# MAG3110.net
KiCad netlist of a schematic drawn in EAGLE
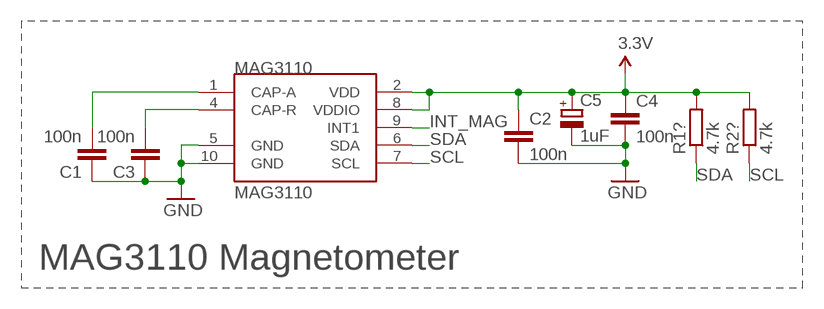
[diagram p0: schematic, sheet 1]

(export (version "E")
  (design (tool "Eeschema 10.0.6"))
  (components
    (comp (ref "C1")
      (value "100n")
      (footprint "eagle-import:C0805")
      (libsource (lib "eagle-import") (part "C-EUC0805"))
    )
    (comp (ref "C2")
      (value "100n")
      (footprint "eagle-import:C0805")
      (libsource (lib "eagle-import") (part "C-EUC0805"))
    )
    (comp (ref "C3")
      (value "100n")
      (footprint "eagle-import:C0805")
      (libsource (lib "eagle-import") (part "C-EUC0805"))
    )
    (comp (ref "C4")
      (value "100n")
      (footprint "eagle-import:C0805")
      (libsource (lib "eagle-import") (part "C-EUC0805"))
    )
    (comp (ref "C5")
      (value "1uF")
      (footprint "eagle-import:SMC_A")
      (libsource (lib "eagle-import") (part "CPOL-EUSMCA"))
    )
    (comp (ref "MAG3110")
      (value "MAG3110")
      (footprint "eagle-import:DFN-10")
      (libsource (lib "eagle-import") (part "MAG3110"))
    )
    (comp (ref "R1?")
      (value "4.7k")
      (footprint "eagle-import:R0805")
      (libsource (lib "eagle-import") (part "R-EU_R0805"))
    )
    (comp (ref "R2?")
      (value "4.7k")
      (footprint "eagle-import:R0805")
      (libsource (lib "eagle-import") (part "R-EU_R0805"))
    )
  )
  (nets
    (net (code "1") (name "/INT_MAG") (class "Default")
      (node (ref "MAG3110") (pin "9") (pinfunction "INT1_9") (pintype "bidirectional"))
    )
    (net (code "2") (name "/SCL") (class "Default")
      (node (ref "MAG3110") (pin "7") (pinfunction "SCL_7") (pintype "bidirectional"))
      (node (ref "R2?") (pin "1") (pinfunction "1_1") (pintype "passive"))
    )
    (net (code "3") (name "/SDA") (class "Default")
      (node (ref "MAG3110") (pin "6") (pinfunction "SDA_6") (pintype "bidirectional"))
      (node (ref "R1?") (pin "1") (pinfunction "1_1") (pintype "passive"))
    )
    (net (code "4") (name "3.3V") (class "Default")
      (node (ref "C2") (pin "1") (pinfunction "1_1") (pintype "passive"))
      (node (ref "C4") (pin "1") (pinfunction "1_1") (pintype "passive"))
      (node (ref "C5") (pin "+") (pinfunction "+_+") (pintype "passive"))
      (node (ref "MAG3110") (pin "2") (pinfunction "VDD_2") (pintype "bidirectional"))
      (node (ref "MAG3110") (pin "8") (pinfunction "VDDIO_8") (pintype "bidirectional"))
      (node (ref "R1?") (pin "2") (pinfunction "2_2") (pintype "passive"))
      (node (ref "R2?") (pin "2") (pinfunction "2_2") (pintype "passive"))
    )
    (net (code "5") (name "GND") (class "Default")
      (node (ref "C1") (pin "1") (pinfunction "1_1") (pintype "passive"))
      (node (ref "C2") (pin "2") (pinfunction "2_2") (pintype "passive"))
      (node (ref "C3") (pin "1") (pinfunction "1_1") (pintype "passive"))
      (node (ref "C4") (pin "2") (pinfunction "2_2") (pintype "passive"))
      (node (ref "C5") (pin "-") (pinfunction "-_-") (pintype "passive"))
      (node (ref "MAG3110") (pin "10") (pinfunction "GND_10") (pintype "bidirectional"))
      (node (ref "MAG3110") (pin "5") (pinfunction "GND_5") (pintype "bidirectional"))
    )
    (net (code "6") (name "Net-(MAG3110-CAP-A)") (class "Default")
      (node (ref "C1") (pin "2") (pinfunction "2_2") (pintype "passive"))
      (node (ref "MAG3110") (pin "1") (pinfunction "CAP-A_1") (pintype "bidirectional"))
    )
    (net (code "7") (name "Net-(MAG3110-CAP-R)") (class "Default")
      (node (ref "C3") (pin "2") (pinfunction "2_2") (pintype "passive"))
      (node (ref "MAG3110") (pin "4") (pinfunction "CAP-R_4") (pintype "bidirectional"))
    )
  )
)
